# power_supply.net
KiCad netlist of a schematic drawn in Altium Designer
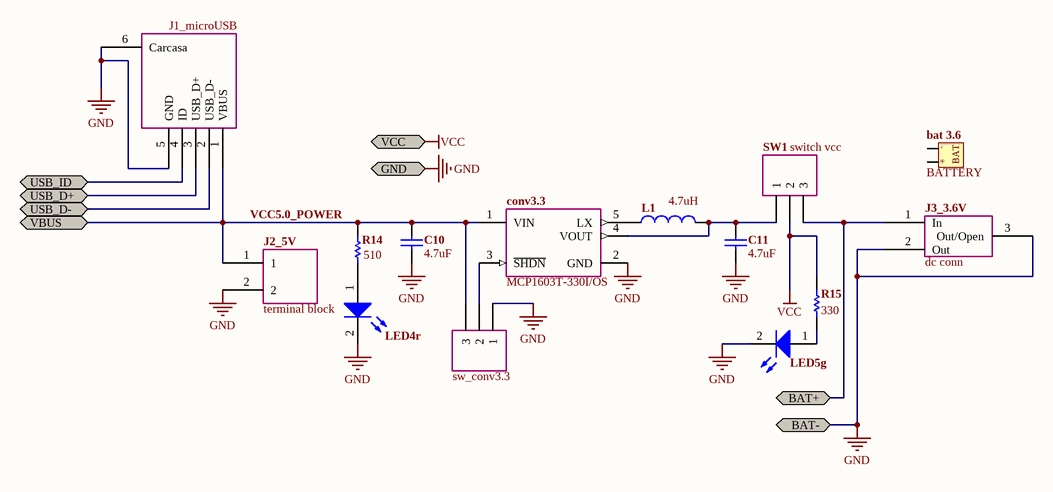
[diagram p0: power_supply.SchDoc]

(export (version "E")
  (design (tool "Eeschema 10.0.6"))
  (components
    (comp (ref "bat 3.6")
      (value "BATTERY")
      (footprint "BATTERY HOLDER 3 cells")
      (libsource (lib "agus_lib") (part "BATTERY"))
    )
    (comp (ref "C10")
      (value "4.7uF")
      (footprint "1608[0603]")
      (description "Capacitor")
      (fields (field (name "Comment") "Cap") (field (name "PUBLISHER") "Altium Limited"))
      (libsource (lib "Miscellaneous Devices") (part "Cap"))
    )
    (comp (ref "C11")
      (value "4.7uF")
      (footprint "1608[0603]")
      (description "Capacitor")
      (fields (field (name "Comment") "Cap") (field (name "PUBLISHER") "Altium Limited"))
      (libsource (lib "Miscellaneous Devices") (part "Cap"))
    )
    (comp (ref "conv3.3")
      (value "MCP1603T-330I/OS")
      (footprint "TSOT-OS5_N")
      (description "500mA Synchronous Buck Regulator, 3.3V, 2.0 MHz, 5-Pin TSOT, Industrial Temperature, Tape and Reel")
      (fields (field (name "PUBLISHER") "Altium Limited"))
      (libsource (lib "PlacaBase_agus") (part "MCP1603T-330I/OS"))
    )
    (comp (ref "J1_microUSB")
      (value "J1_microUSB")
      (footprint "microUSB AB")
      (libsource (lib "PlacaBase_agus") (part "USB micro AB"))
    )
    (comp (ref "J2_5V")
      (value "terminal block")
      (footprint "Conector ED-1631")
      (description "Terminal Block 2 vías, 5mm")
      (libsource (lib "PlacaBase_agus") (part "Conector ED-1631"))
    )
    (comp (ref "J3_3.6V")
      (value "dc conn")
      (footprint "DC Connector")
      (libsource (lib "PlacaBase_agus") (part "DC Connector"))
    )
    (comp (ref "L1")
      (value "4.7uH")
      (footprint "CD3225-1210")
      (description "Inductor")
      (fields
        (field (name "MANUFACTURER") "Generic Components")
        (field (name "Comment") "L")
        (field (name "PUBLISHER") "Altium Hobart Technology Centre")
      )
      (libsource (lib "agus_lib") (part "L"))
    )
    (comp (ref "LED4r")
      (value "LED_SMD_Hg")
      (footprint "1608[0603]")
      (description "Typical BLUE SiC LED")
      (fields
        (field (name "MANUFACTURER") "Generic Components")
        (field (name "PUBLISHER") "Altium Hobart Technology Centre")
      )
      (libsource (lib "LSI") (part "LED_SMD_Hg"))
    )
    (comp (ref "LED5g")
      (value "LED_SMD_Hg")
      (footprint "1608[0603]")
      (description "Typical BLUE SiC LED")
      (fields
        (field (name "MANUFACTURER") "Generic Components")
        (field (name "PUBLISHER") "Altium Hobart Technology Centre")
      )
      (libsource (lib "LSI") (part "LED_SMD_Hg"))
    )
    (comp (ref "R14")
      (value "510")
      (footprint "1608[0603]")
      (description "Resistor")
      (fields (field (name "Comment") "Res1") (field (name "PUBLISHER") "Altium Limited"))
      (libsource (lib "Miscellaneous Devices") (part "Res1"))
    )
    (comp (ref "R15")
      (value "330")
      (footprint "1608[0603]")
      (description "Resistor")
      (fields
        (field (name "MANUFACTURER") "Generic Components")
        (field (name "Comment") "R")
        (field (name "PUBLISHER") "Altium Hobart Technology Centre")
      )
      (libsource (lib "LSI") (part "R"))
    )
    (comp (ref "SW1")
      (value "switch vcc")
      (footprint "SWITCH-2")
      (description "Header, 3-Pin")
      (fields (field (name "PUBLISHER") "Altium Limited"))
      (libsource (lib "") (part "SWITCH-2_1"))
    )
    (comp (ref "SW2")
      (value "sw_conv3.3")
      (footprint "HDR1X3")
      (description "Header, 3-Pin")
      (fields (field (name "PUBLISHER") "Altium Limited"))
      (libsource (lib "PlacaBase_agus") (part "SWITCH-2"))
    )
  )
  (nets
    (net (code "1") (name "/BAT+") (class "Default")
      (node (ref "J3_3.6V") (pin "1") (pinfunction "In_1") (pintype "power_in"))
      (node (ref "SW1") (pin "3") (pinfunction "3_3") (pintype "passive"))
    )
    (net (code "2") (name "/USB_D+") (class "Default")
      (node (ref "J1_microUSB") (pin "3") (pinfunction "USB_D+_3") (pintype "passive"))
    )
    (net (code "3") (name "/USB_D-") (class "Default")
      (node (ref "J1_microUSB") (pin "2") (pinfunction "USB_D-_2") (pintype "passive"))
    )
    (net (code "4") (name "/USB_ID") (class "Default")
      (node (ref "J1_microUSB") (pin "4") (pinfunction "ID_4") (pintype "passive"))
    )
    (net (code "5") (name "/VCC5.0_POWER") (class "Default")
      (node (ref "C10") (pin "2") (pinfunction "2_2") (pintype "passive"))
      (node (ref "J1_microUSB") (pin "1") (pinfunction "VBUS_1") (pintype "passive"))
      (node (ref "J2_5V") (pin "1") (pinfunction "1_1") (pintype "passive"))
      (node (ref "R14") (pin "1") (pinfunction "1_1") (pintype "passive"))
      (node (ref "SW2") (pin "3") (pinfunction "3_3") (pintype "passive"))
      (node (ref "conv3.3") (pin "1") (pinfunction "VIN_1") (pintype "power_in"))
    )
    (net (code "6") (name "GND") (class "Default")
      (node (ref "C10") (pin "1") (pinfunction "1_1") (pintype "passive"))
      (node (ref "C11") (pin "1") (pinfunction "1_1") (pintype "passive"))
      (node (ref "J1_microUSB") (pin "5") (pinfunction "GND_5") (pintype "passive"))
      (node (ref "J1_microUSB") (pin "6") (pinfunction "Carcasa_6") (pintype "passive"))
      (node (ref "J2_5V") (pin "2") (pinfunction "2_2") (pintype "passive"))
      (node (ref "J3_3.6V") (pin "2") (pinfunction "Out_2") (pintype "power_in"))
      (node (ref "J3_3.6V") (pin "3") (pinfunction "Out/Open_3") (pintype "power_in"))
      (node (ref "LED4r") (pin "2") (pinfunction "K_2") (pintype "passive"))
      (node (ref "LED5g") (pin "2") (pinfunction "K_2") (pintype "passive"))
      (node (ref "SW2") (pin "1") (pinfunction "1_1") (pintype "passive"))
      (node (ref "conv3.3") (pin "2") (pinfunction "GND_2") (pintype "power_in"))
    )
    (net (code "7") (name "Net-(LED4r-A)") (class "Default")
      (node (ref "LED4r") (pin "1") (pinfunction "A_1") (pintype "passive"))
      (node (ref "R14") (pin "2") (pinfunction "2_2") (pintype "passive"))
    )
    (net (code "8") (name "Net-(LED5g-A)") (class "Default")
      (node (ref "LED5g") (pin "1") (pinfunction "A_1") (pintype "passive"))
      (node (ref "R15") (pin "1") (pinfunction "1_1") (pintype "passive"))
    )
    (net (code "9") (name "Net-(conv3.3-LX)") (class "Default")
      (node (ref "L1") (pin "1") (pinfunction "1_1") (pintype "passive"))
      (node (ref "conv3.3") (pin "5") (pinfunction "LX_5") (pintype "output"))
    )
    (net (code "10") (name "Net-(conv3.3-VOUT)") (class "Default")
      (node (ref "C11") (pin "2") (pinfunction "2_2") (pintype "passive"))
      (node (ref "L1") (pin "2") (pinfunction "2_2") (pintype "passive"))
      (node (ref "SW1") (pin "1") (pinfunction "1_1") (pintype "passive"))
      (node (ref "conv3.3") (pin "4") (pinfunction "VOUT_4") (pintype "output"))
    )
    (net (code "11") (name "Net-(conv3.3-~{SHDN})") (class "Default")
      (node (ref "SW2") (pin "2") (pinfunction "2_2") (pintype "passive"))
      (node (ref "conv3.3") (pin "3") (pinfunction "~{SHDN}_3") (pintype "input"))
    )
    (net (code "12") (name "VCC") (class "Default")
      (node (ref "R15") (pin "2") (pinfunction "2_2") (pintype "passive"))
      (node (ref "SW1") (pin "2") (pinfunction "2_2") (pintype "passive"))
    )
  )
)
